# supply0.net
KiCad netlist of a schematic drawn in Altium Designer
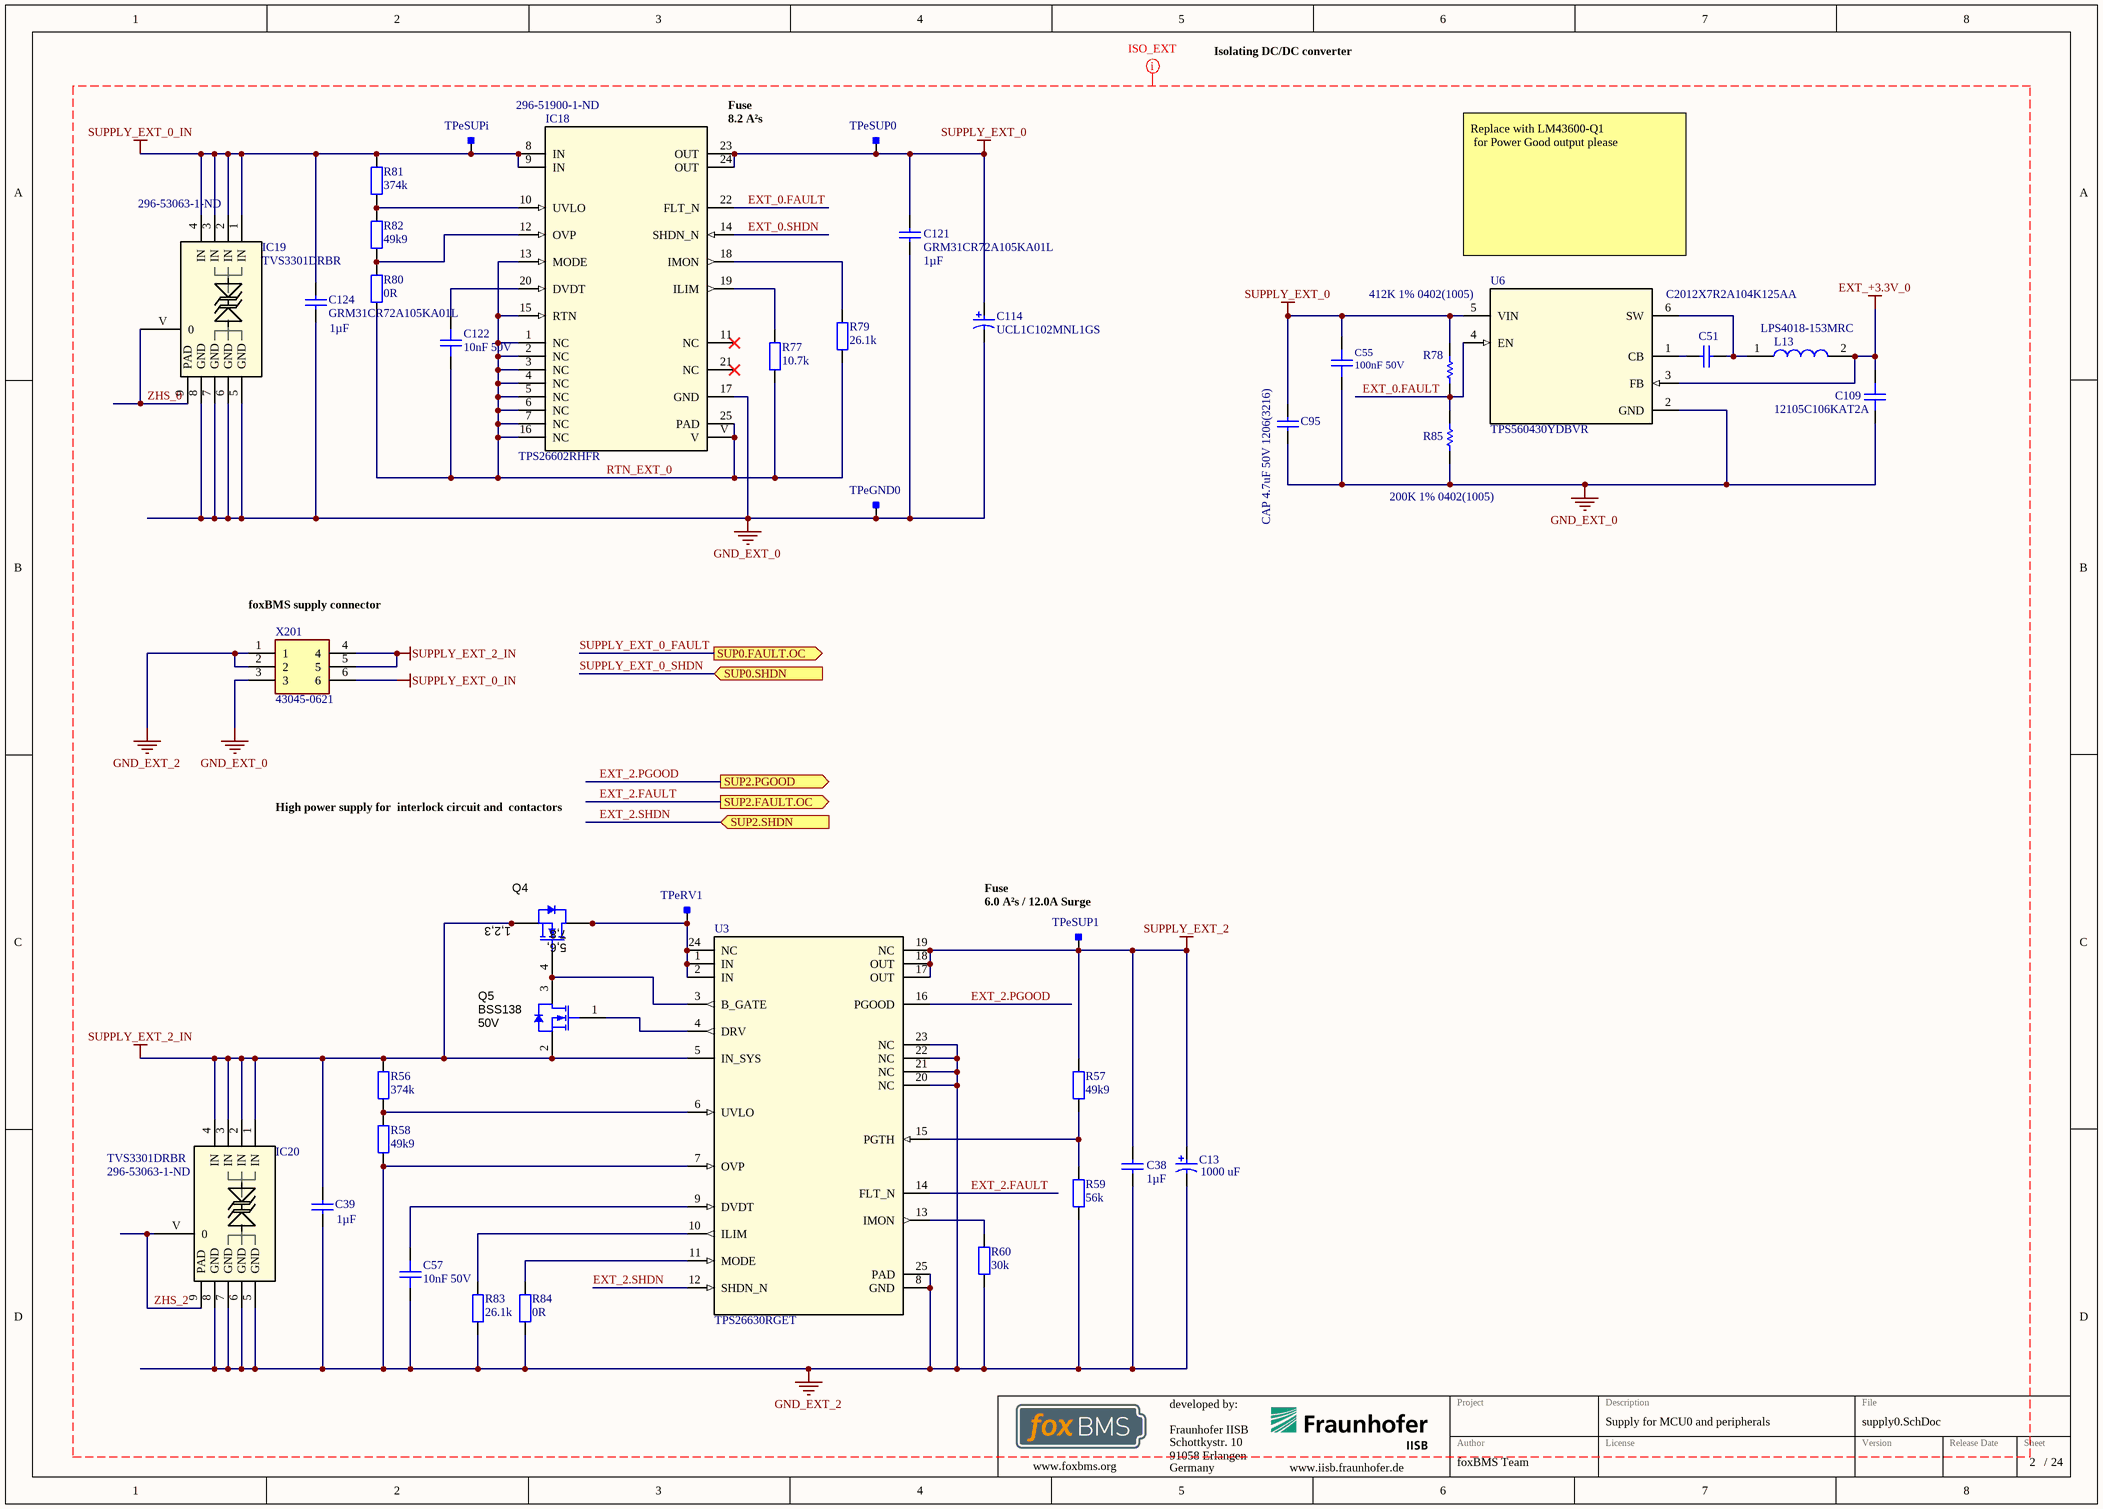
[diagram p0: supply0.SchDoc]

(export (version "E")
  (design (tool "Eeschema 10.0.6"))
  (components
    (comp (ref "C13")
      (value "UCL1C102MNL1GS")
      (footprint "NIC-UCL-10x13.5-2_V")
      (fields (field (name "MANUFACTURER") "Nichicon") (field (name "RATED CAPACITANCE") "1000 uF"))
      (libsource (lib "Altium Content Vault") (part "NIC-CAP-P-2"))
    )
    (comp (ref "C38")
      (value "GRM31CR72A105KA01L")
      (footprint "CAPC3216X180X55ML20T25")
      (description "Chip Capacitor, 1 uF, +/- 10%, 100 V, -55 to 125 degC, 1206 (3216 Metric), RoHS, Tape and Reel")
      (fields
        (field (name "TOLERANCE") "±10%")
        (field (name "MANUFACTURER") "Murata")
        (field (name "CAPACITANCE") "1µF")
      )
      (libsource (lib "master-010106") (part "CAP-NP-2"))
    )
    (comp (ref "C39")
      (value "GRM31CR72A105KA01L")
      (footprint "CAPC3216X180X55ML20T25")
      (description "Chip Capacitor, 1 uF, +/- 10%, 100 V, -55 to 125 degC, 1206 (3216 Metric), RoHS, Tape and Reel")
      (fields
        (field (name "TOLERANCE") "±10%")
        (field (name "MANUFACTURER") "Murata")
        (field (name "CAPACITANCE") "1µF")
      )
      (libsource (lib "master-010106") (part "CAP-NP-2"))
    )
    (comp (ref "C51")
      (value "C2012X7R2A104K125AA")
      (footprint "CAPC2013X145X20ML20")
      (description "Chip Capacitor, 100 nF, +/- 10%, 100 V, -55 to 1255 degC, 0805 (2012 Metric), RoHS, Tape and Reel")
      (fields (field (name "MANUFACTURER") "TDK") (field (name "TOLERANCE") "±10%"))
      (libsource (lib "Altium Content Vault") (part "CAP-NP-2"))
    )
    (comp (ref "C55")
      (value "100nF 50V")
      (footprint "0603C")
      (description "Ceramic, 100nF, ±10%, 50V, X7R, –55 to 125°C, 0603 (1608),RoHS, Automotive")
      (fields (field (name "PART NUMBER") "GCJ188R71H104KA12") (field (name "TOLERANCE") "±10%"))
      (libsource (lib "master-010106") (part "gen_C_ceramic_100n_50V_X7R_0603"))
    )
    (comp (ref "C57")
      (value "10nF 50V")
      (footprint "0402C")
      (description "Ceramic, 10nF, ±10%, 50V, X7R, –55 to 125°C, 0402 (1005),RoHS, Automotive")
      (fields (field (name "PART NUMBER") "GRT155R71H104KE01"))
      (libsource (lib "master-010106") (part "gen_C_ceramic_10n_50V_X7R_0402"))
    )
    (comp (ref "C95")
      (value "CAP 4.7uF 50V 1206(3216)")
      (footprint "CAPC1206(3216)190_N")
      (description "CAP 4.7uF 50V ±10% 1206 (3216 Metric) Thickness 1.9mm SMD")
      (fields (field (name "TOLERANCE") "Â±10%"))
      (libsource (lib "Altium Content Vault") (part "CAP"))
    )
    (comp (ref "C109")
      (value "12105C106KAT2A")
      (footprint "CAPC3225X279X50LL20T25")
      (description "Ceramic, 10uF, 50 V, -55 to 125 degC, 2-Pin SMD (1210), RoHS, Tape and Reel")
      (fields (field (name "TOLERANCE") "±10%") (field (name "MANUFACTURER") "AVX"))
      (libsource (lib "master-010106") (part "gen_C_ceramic_10u_50V_X7R_1210"))
    )
    (comp (ref "C114")
      (value "UCL1C102MNL1GS")
      (footprint "NIC-UCL-10x13.5-2_V")
      (fields (field (name "MANUFACTURER") "Nichicon"))
      (libsource (lib "Altium Content Vault") (part "NIC-CAP-P-2"))
    )
    (comp (ref "C121")
      (value "GRM31CR72A105KA01L")
      (footprint "CAPC3216X180X55ML20T25")
      (description "Chip Capacitor, 1 uF, +/- 10%, 100 V, -55 to 125 degC, 1206 (3216 Metric), RoHS, Tape and Reel")
      (fields
        (field (name "TOLERANCE") "±10%")
        (field (name "MANUFACTURER") "Murata")
        (field (name "CAPACITANCE") "1µF")
      )
      (libsource (lib "master-010106") (part "CAP-NP-2"))
    )
    (comp (ref "C122")
      (value "10nF 50V")
      (footprint "0402C")
      (description "Ceramic, 10nF, ±10%, 50V, X7R, –55 to 125°C, 0402 (1005),RoHS, Automotive")
      (fields (field (name "PART NUMBER") "GRT155R71H104KE01"))
      (libsource (lib "master-010106") (part "gen_C_ceramic_10n_50V_X7R_0402"))
    )
    (comp (ref "C124")
      (value "GRM31CR72A105KA01L")
      (footprint "CAPC3216X180X55ML20T25")
      (description "Chip Capacitor, 1 uF, +/- 10%, 100 V, -55 to 125 degC, 1206 (3216 Metric), RoHS, Tape and Reel")
      (fields
        (field (name "TOLERANCE") "±10%")
        (field (name "MANUFACTURER") "Murata")
        (field (name "CAPACITANCE") "1µF")
      )
      (libsource (lib "master-010106") (part "CAP-NP-2"))
    )
    (comp (ref "IC18")
      (value "TPS26602RHFR")
      (footprint "RHF0024A")
      (description "37V Clamped input protection")
      (fields
        (field (name "MANUFACTURER") "Texas Instruments")
        (field (name "SUPPLIER PART NUMBER 1") "296-51900-1-ND")
      )
      (libsource (lib "ti-import") (part "TPS26602RHFR"))
    )
    (comp (ref "IC19")
      (value "TVS3301DRBR")
      (footprint "DRB0008F")
      (description "TVS3301 33-V Bidirectional Flat-Clamp Surge Protection Device")
      (fields
        (field (name "MANUFACTURER") "Texas Instruments")
        (field (name "SUPPLIER PART NUMBER 1") "296-53063-1-ND")
      )
      (libsource (lib "ti-import") (part "TVS3301DRVR"))
    )
    (comp (ref "IC20")
      (value "TVS3301DRBR")
      (footprint "DRB0008F")
      (description "TVS3301 33-V Bidirectional Flat-Clamp Surge Protection Device")
      (fields
        (field (name "MANUFACTURER") "Texas Instruments")
        (field (name "SUPPLIER PART NUMBER 1") "296-53063-1-ND")
      )
      (libsource (lib "ti-import") (part "TVS3301DRVR"))
    )
    (comp (ref "L13")
      (value "LPS4018-153MRC")
      (footprint "SamacSys:LPS4018223MRC")
      (description "Inductor 15uH")
      (fields
        (field (name "MANUFACTURER_PART_NUMBER") "LPS4018-223MRC")
        (field (name "MOUSER PART NUMBER") "994-LPS4018-223MRC")
      )
      (libsource (lib "*") (part "LPS4018-223MRC"))
    )
    (comp (ref "Q4")
      (value "CSD17308Q3")
      (footprint "TRANS_NexFET_Q3")
      (description "MOSFET, N-CH, 30V, 47A, SON 3.3x3.3mm")
      (fields
        (field (name "MANUFACTURER") "Texas Instruments")
        (field (name "PUBLISHER") "Texas Instruments")
      )
      (libsource (lib "master-010106") (part "CSD17308Q3"))
    )
    (comp (ref "Q5")
      (value "BSS138")
      (footprint "SOT-23")
      (description "MOSFET, N-CH, 50V, 0.22A, SOT-23")
      (fields
        (field (name "MANUFACTURER") "Fairchild Semiconductor")
        (field (name "ALTIUM_VALUE") "50V")
        (field (name "PUBLISHER") "Texas Instruments")
      )
      (libsource (lib "master-010106") (part "BSS138"))
    )
    (comp (ref "R56")
      (value "374k")
      (footprint "0402R")
      (description "SMD Resistor 374k 0402")
      (fields (field (name "PART NUMBER") "gen_R_374k_0402"))
      (libsource (lib "master-010106") (part "gen_R_374k_0402"))
    )
    (comp (ref "R57")
      (value "49k9")
      (footprint "0402R")
      (description "SMD Resistor 49.9k 0402")
      (fields (field (name "PART NUMBER") "gen_R_49k9_0402"))
      (libsource (lib "master-010106") (part "gen_R_49k9_0402"))
    )
    (comp (ref "R58")
      (value "49k9")
      (footprint "0402R")
      (description "SMD Resistor 49.9k 0402")
      (fields (field (name "PART NUMBER") "gen_R_49k9_0402"))
      (libsource (lib "master-010106") (part "gen_R_49k9_0402"))
    )
    (comp (ref "R59")
      (value "56k")
      (footprint "0402R")
      (description "SMD Resistor 49.9k 0402")
      (fields (field (name "PART NUMBER") "gen_R_49k9_0402"))
      (libsource (lib "master-010106") (part "gen_R_49k9_0402"))
    )
    (comp (ref "R60")
      (value "30k")
      (footprint "0402R")
      (description "SMD Resistor 30k 0402")
      (fields (field (name "PART NUMBER") "gen_R_10.7k_0402"))
      (libsource (lib "master-010106") (part "gen_R_10k7_0402"))
    )
    (comp (ref "R77")
      (value "10.7k")
      (footprint "0402R")
      (description "SMD Resistor 10.7k 0402")
      (fields (field (name "PART NUMBER") "gen_R_10.7k_0402"))
      (libsource (lib "master-010106") (part "gen_R_10k7_0402"))
    )
    (comp (ref "R78")
      (value "412K 1% 0402(1005)")
      (footprint "RESC0402(1005)_L")
      (description "412K 0.063W 1% 0402 (1005 Metric)  SMD")
      (fields (field (name "TOLERANCE") "1 %") (field (name "POWER") "0.063 W"))
      (libsource (lib "Altium Content Vault") (part "RES"))
    )
    (comp (ref "R79")
      (value "26.1k")
      (footprint "0402R")
      (description "SMD Resistor 26.1k 0402")
      (fields (field (name "PART NUMBER") "gen_R_26.1k_0402"))
      (libsource (lib "master-010106") (part "gen_R_26k1_0402"))
    )
    (comp (ref "R80")
      (value "0R")
      (footprint "0402R")
      (description "SMD Resistor 0R 0402")
      (fields (field (name "PART NUMBER") "gen_R_0R_0402"))
      (libsource (lib "master-010106") (part "gen_R_0R_0402"))
    )
    (comp (ref "R81")
      (value "374k")
      (footprint "0402R")
      (description "SMD Resistor 374k 0402")
      (fields (field (name "PART NUMBER") "gen_R_374k_0402"))
      (libsource (lib "master-010106") (part "gen_R_374k_0402"))
    )
    (comp (ref "R82")
      (value "49k9")
      (footprint "0402R")
      (description "SMD Resistor 49.9k 0402")
      (fields (field (name "PART NUMBER") "gen_R_49k9_0402"))
      (libsource (lib "master-010106") (part "gen_R_49k9_0402"))
    )
    (comp (ref "R83")
      (value "26.1k")
      (footprint "0402R")
      (description "SMD Resistor 26.1k 0402")
      (fields (field (name "PART NUMBER") "gen_R_26.1k_0402"))
      (libsource (lib "master-010106") (part "gen_R_26k1_0402"))
    )
    (comp (ref "R84")
      (value "0R")
      (footprint "0402R")
      (description "SMD Resistor 0R 0402")
      (fields (field (name "PART NUMBER") "gen_R_0R_0402"))
      (libsource (lib "master-010106") (part "gen_R_0R_0402"))
    )
    (comp (ref "R85")
      (value "200K 1% 0402(1005)")
      (footprint "RESC0402(1005)_L")
      (description "200K 0.063W 1% 0402 (1005 Metric)  SMD")
      (fields (field (name "TOLERANCE") "1 %") (field (name "POWER") "0.063 W"))
      (libsource (lib "Altium Content Vault") (part "RES"))
    )
    (comp (ref "TPeGND0")
      (value "Testpoint_Square")
      (footprint "Testpoint_S1")
      (description "Testpoint, square")
      (libsource (lib "OE750") (part "Testpoint_Square"))
    )
    (comp (ref "TPeRV1")
      (value "Testpoint_Square")
      (footprint "Testpoint_S1")
      (description "Testpoint, square")
      (libsource (lib "OE750") (part "Testpoint_Square"))
    )
    (comp (ref "TPeSUP0")
      (value "Testpoint_Square")
      (footprint "Testpoint_S1")
      (description "Testpoint, square")
      (libsource (lib "OE750") (part "Testpoint_Square"))
    )
    (comp (ref "TPeSUP1")
      (value "Testpoint_Square")
      (footprint "Testpoint_S1")
      (description "Testpoint, square")
      (libsource (lib "OE750") (part "Testpoint_Square"))
    )
    (comp (ref "TPeSUPi")
      (value "Testpoint_Square")
      (footprint "Testpoint_S1")
      (description "Testpoint, square")
      (libsource (lib "OE750") (part "Testpoint_Square"))
    )
    (comp (ref "U3")
      (value "TPS26630RGET")
      (footprint "RGE0024H")
      (description "Imported")
      (fields (field (name "MANUFACTURER") "Texas Instruments") (field (name "PARTNUMBER") "TPS26630RGER"))
      (libsource (lib "ti-import") (part "TPS26630RGET"))
    )
    (comp (ref "U6")
      (value "TPS560430YDBVR")
      (footprint "DBV0006A_N")
      (description "Imported")
      (fields (field (name "MANUFACTURER") "Texas Instruments"))
      (libsource (lib "ti-import") (part "TPS560430YDBVR"))
    )
    (comp (ref "X201")
      (value "43045-0621")
      (footprint "43045-0621")
      (fields (field (name "MOUSER PART NUMBER") "538-43045-0621") (field (name "RS PART NUMBER") "6700380"))
      (libsource (lib "SamacSys") (part "43045-0621"))
    )
  )
  (nets
    (net (code "1") (name "/EXT_0.FAULT") (class "Default")
      (node (ref "IC18") (pin "22") (pinfunction "FLT_N_22") (pintype "open_collector"))
      (node (ref "R78") (pin "1") (pinfunction "1_1") (pintype "passive"))
      (node (ref "R85") (pin "2") (pinfunction "2_2") (pintype "passive"))
      (node (ref "U6") (pin "4") (pinfunction "EN_4") (pintype "input"))
    )
    (net (code "2") (name "/EXT_0.SHDN") (class "Default")
      (node (ref "IC18") (pin "14") (pinfunction "SHDN_N_14") (pintype "input"))
    )
    (net (code "3") (name "/EXT_2.FAULT") (class "Default")
      (node (ref "U3") (pin "14") (pinfunction "FLT_N_14") (pintype "open_collector"))
    )
    (net (code "4") (name "/EXT_2.PGOOD") (class "Default")
      (node (ref "U3") (pin "16") (pinfunction "PGOOD_16") (pintype "open_collector"))
    )
    (net (code "5") (name "/EXT_2.SHDN") (class "Default")
      (node (ref "U3") (pin "12") (pinfunction "SHDN_N_12") (pintype "input"))
    )
    (net (code "6") (name "/RTN_EXT_0") (class "Default")
      (node (ref "C122") (pin "2") (pinfunction "2_2") (pintype "passive"))
      (node (ref "IC18") (pin "1") (pinfunction "NC_1") (pintype "passive"))
      (node (ref "IC18") (pin "13") (pinfunction "MODE_13") (pintype "input"))
      (node (ref "IC18") (pin "15") (pinfunction "RTN_15") (pintype "input"))
      (node (ref "IC18") (pin "16") (pinfunction "NC_16") (pintype "passive"))
      (node (ref "IC18") (pin "2") (pinfunction "NC_2") (pintype "passive"))
      (node (ref "IC18") (pin "25") (pinfunction "PAD_25") (pintype "power_in"))
      (node (ref "IC18") (pin "3") (pinfunction "NC_3") (pintype "passive"))
      (node (ref "IC18") (pin "4") (pinfunction "NC_4") (pintype "passive"))
      (node (ref "IC18") (pin "5") (pinfunction "NC_5") (pintype "passive"))
      (node (ref "IC18") (pin "6") (pinfunction "NC_6") (pintype "passive"))
      (node (ref "IC18") (pin "7") (pinfunction "NC_7") (pintype "passive"))
      (node (ref "IC18") (pin "V") (pinfunction "V_V") (pintype "passive"))
      (node (ref "R77") (pin "1") (pinfunction "1_1") (pintype "passive"))
      (node (ref "R79") (pin "1") (pinfunction "1_1") (pintype "passive"))
      (node (ref "R80") (pin "1") (pinfunction "1_1") (pintype "passive"))
    )
    (net (code "9") (name "/ZHS_0") (class "Default")
      (node (ref "IC19") (pin "9") (pinfunction "PAD_9") (pintype "passive"))
      (node (ref "IC19") (pin "V") (pinfunction "0_V") (pintype "passive"))
    )
    (net (code "10") (name "/ZHS_2") (class "Default")
      (node (ref "IC20") (pin "9") (pinfunction "PAD_9") (pintype "passive"))
      (node (ref "IC20") (pin "V") (pinfunction "0_V") (pintype "passive"))
    )
    (net (code "11") (name "EXT_+3.3V_0") (class "Default")
      (node (ref "C109") (pin "2") (pinfunction "2_2") (pintype "passive"))
      (node (ref "L13") (pin "2") (pinfunction "2_2") (pintype "passive"))
      (node (ref "U6") (pin "3") (pinfunction "FB_3") (pintype "input"))
    )
    (net (code "12") (name "GND_EXT_0") (class "Default")
      (node (ref "C109") (pin "1") (pinfunction "1_1") (pintype "passive"))
      (node (ref "C114") (pin "2") (pinfunction "2_2") (pintype "passive"))
      (node (ref "C121") (pin "1") (pinfunction "1_1") (pintype "passive"))
      (node (ref "C124") (pin "1") (pinfunction "1_1") (pintype "passive"))
      (node (ref "C55") (pin "1") (pinfunction "1_1") (pintype "passive"))
      (node (ref "C95") (pin "1") (pinfunction "1_1") (pintype "passive"))
      (node (ref "IC18") (pin "17") (pinfunction "GND_17") (pintype "power_in"))
      (node (ref "IC19") (pin "5") (pinfunction "GND_5") (pintype "passive"))
      (node (ref "IC19") (pin "6") (pinfunction "GND_6") (pintype "passive"))
      (node (ref "IC19") (pin "7") (pinfunction "GND_7") (pintype "passive"))
      (node (ref "IC19") (pin "8") (pinfunction "GND_8") (pintype "passive"))
      (node (ref "R85") (pin "1") (pinfunction "1_1") (pintype "passive"))
      (node (ref "TPeGND0") (pin "1") (pinfunction "1_1") (pintype "passive"))
      (node (ref "U6") (pin "2") (pinfunction "GND_2") (pintype "power_in"))
      (node (ref "X201") (pin "3") (pinfunction "3_3") (pintype "passive"))
    )
    (net (code "13") (name "GND_EXT_2") (class "Default")
      (node (ref "C13") (pin "2") (pinfunction "2_2") (pintype "passive"))
      (node (ref "C38") (pin "1") (pinfunction "1_1") (pintype "passive"))
      (node (ref "C39") (pin "1") (pinfunction "1_1") (pintype "passive"))
      (node (ref "C57") (pin "2") (pinfunction "2_2") (pintype "passive"))
      (node (ref "IC20") (pin "5") (pinfunction "GND_5") (pintype "passive"))
      (node (ref "IC20") (pin "6") (pinfunction "GND_6") (pintype "passive"))
      (node (ref "IC20") (pin "7") (pinfunction "GND_7") (pintype "passive"))
      (node (ref "IC20") (pin "8") (pinfunction "GND_8") (pintype "passive"))
      (node (ref "R58") (pin "1") (pinfunction "1_1") (pintype "passive"))
      (node (ref "R59") (pin "1") (pinfunction "1_1") (pintype "passive"))
      (node (ref "R60") (pin "1") (pinfunction "1_1") (pintype "passive"))
      (node (ref "R83") (pin "1") (pinfunction "1_1") (pintype "passive"))
      (node (ref "R84") (pin "1") (pinfunction "1_1") (pintype "passive"))
      (node (ref "U3") (pin "20") (pinfunction "NC_20") (pintype "passive"))
      (node (ref "U3") (pin "21") (pinfunction "NC_21") (pintype "passive"))
      (node (ref "U3") (pin "22") (pinfunction "NC_22") (pintype "passive"))
      (node (ref "U3") (pin "23") (pinfunction "NC_23") (pintype "passive"))
      (node (ref "U3") (pin "25") (pinfunction "PAD_25") (pintype "power_in"))
      (node (ref "U3") (pin "7") (pinfunction "OVP_7") (pintype "input"))
      (node (ref "U3") (pin "8") (pinfunction "GND_8") (pintype "power_in"))
      (node (ref "X201") (pin "1") (pinfunction "1_1") (pintype "passive"))
      (node (ref "X201") (pin "2") (pinfunction "2_2") (pintype "passive"))
    )
    (net (code "14") (name "Net-(IC18-DVDT)") (class "Default")
      (node (ref "C122") (pin "1") (pinfunction "1_1") (pintype "passive"))
      (node (ref "IC18") (pin "20") (pinfunction "DVDT_20") (pintype "input"))
    )
    (net (code "15") (name "Net-(IC18-ILIM)") (class "Default")
      (node (ref "IC18") (pin "19") (pinfunction "ILIM_19") (pintype "output"))
      (node (ref "R77") (pin "2") (pinfunction "2_2") (pintype "passive"))
    )
    (net (code "16") (name "Net-(IC18-IMON)") (class "Default")
      (node (ref "IC18") (pin "18") (pinfunction "IMON_18") (pintype "output"))
      (node (ref "R79") (pin "2") (pinfunction "2_2") (pintype "passive"))
    )
    (net (code "17") (name "Net-(IC18-OVP)") (class "Default")
      (node (ref "IC18") (pin "12") (pinfunction "OVP_12") (pintype "input"))
      (node (ref "R80") (pin "2") (pinfunction "2_2") (pintype "passive"))
      (node (ref "R82") (pin "1") (pinfunction "1_1") (pintype "passive"))
    )
    (net (code "18") (name "Net-(IC18-UVLO)") (class "Default")
      (node (ref "IC18") (pin "10") (pinfunction "UVLO_10") (pintype "input"))
      (node (ref "R81") (pin "1") (pinfunction "1_1") (pintype "passive"))
      (node (ref "R82") (pin "2") (pinfunction "2_2") (pintype "passive"))
    )
    (net (code "19") (name "Net-(Q4-D-Pad5)") (class "Default")
      (node (ref "Q4") (pin "5") (pinfunction "D_5") (pintype "passive"))
      (node (ref "Q4") (pin "6") (pinfunction "D_6") (pintype "passive"))
      (node (ref "Q4") (pin "7") (pinfunction "D_7") (pintype "passive"))
      (node (ref "Q4") (pin "8") (pinfunction "D_8") (pintype "passive"))
      (node (ref "TPeRV1") (pin "1") (pinfunction "1_1") (pintype "passive"))
      (node (ref "U3") (pin "1") (pinfunction "IN_1") (pintype "power_in"))
      (node (ref "U3") (pin "2") (pinfunction "IN_2") (pintype "power_in"))
      (node (ref "U3") (pin "24") (pinfunction "NC_24") (pintype "passive"))
    )
    (net (code "20") (name "Net-(Q4-G)") (class "Default")
      (node (ref "Q4") (pin "4") (pinfunction "G_4") (pintype "passive"))
      (node (ref "Q5") (pin "3") (pinfunction "D_3") (pintype "passive"))
      (node (ref "U3") (pin "3") (pinfunction "B_GATE_3") (pintype "output"))
    )
    (net (code "21") (name "Net-(Q5-G)") (class "Default")
      (node (ref "Q5") (pin "1") (pinfunction "G_1") (pintype "passive"))
      (node (ref "U3") (pin "4") (pinfunction "DRV_4") (pintype "output"))
    )
    (net (code "22") (name "Net-(U3-DVDT)") (class "Default")
      (node (ref "C57") (pin "1") (pinfunction "1_1") (pintype "passive"))
      (node (ref "U3") (pin "9") (pinfunction "DVDT_9") (pintype "input"))
    )
    (net (code "23") (name "Net-(U3-ILIM)") (class "Default")
      (node (ref "R83") (pin "2") (pinfunction "2_2") (pintype "passive"))
      (node (ref "U3") (pin "10") (pinfunction "ILIM_10") (pintype "output"))
    )
    (net (code "24") (name "Net-(U3-IMON)") (class "Default")
      (node (ref "R60") (pin "2") (pinfunction "2_2") (pintype "passive"))
      (node (ref "U3") (pin "13") (pinfunction "IMON_13") (pintype "output"))
    )
    (net (code "25") (name "Net-(U3-MODE)") (class "Default")
      (node (ref "R84") (pin "2") (pinfunction "2_2") (pintype "passive"))
      (node (ref "U3") (pin "11") (pinfunction "MODE_11") (pintype "input"))
    )
    (net (code "26") (name "Net-(U3-PGTH)") (class "Default")
      (node (ref "R57") (pin "1") (pinfunction "1_1") (pintype "passive"))
      (node (ref "R59") (pin "2") (pinfunction "2_2") (pintype "passive"))
      (node (ref "U3") (pin "15") (pinfunction "PGTH_15") (pintype "input"))
    )
    (net (code "27") (name "Net-(U3-UVLO)") (class "Default")
      (node (ref "R56") (pin "1") (pinfunction "1_1") (pintype "passive"))
      (node (ref "R58") (pin "2") (pinfunction "2_2") (pintype "passive"))
      (node (ref "U3") (pin "6") (pinfunction "UVLO_6") (pintype "input"))
    )
    (net (code "28") (name "Net-(U6-CB)") (class "Default")
      (node (ref "C51") (pin "1") (pinfunction "1_1") (pintype "passive"))
      (node (ref "U6") (pin "1") (pinfunction "CB_1") (pintype "power_in"))
    )
    (net (code "29") (name "Net-(U6-SW)") (class "Default")
      (node (ref "C51") (pin "2") (pinfunction "2_2") (pintype "passive"))
      (node (ref "L13") (pin "1") (pinfunction "1_1") (pintype "passive"))
      (node (ref "U6") (pin "6") (pinfunction "SW_6") (pintype "power_in"))
    )
    (net (code "30") (name "SUPPLY_EXT_0") (class "Default")
      (node (ref "C114") (pin "1") (pinfunction "1_1") (pintype "passive"))
      (node (ref "C121") (pin "2") (pinfunction "2_2") (pintype "passive"))
      (node (ref "C55") (pin "2") (pinfunction "2_2") (pintype "passive"))
      (node (ref "C95") (pin "2") (pinfunction "2_2") (pintype "passive"))
      (node (ref "IC18") (pin "23") (pinfunction "OUT_23") (pintype "power_in"))
      (node (ref "IC18") (pin "24") (pinfunction "OUT_24") (pintype "power_in"))
      (node (ref "R78") (pin "2") (pinfunction "2_2") (pintype "passive"))
      (node (ref "TPeSUP0") (pin "1") (pinfunction "1_1") (pintype "passive"))
      (node (ref "U6") (pin "5") (pinfunction "VIN_5") (pintype "power_in"))
    )
    (net (code "31") (name "SUPPLY_EXT_0_IN") (class "Default")
      (node (ref "C124") (pin "2") (pinfunction "2_2") (pintype "passive"))
      (node (ref "IC18") (pin "8") (pinfunction "IN_8") (pintype "power_in"))
      (node (ref "IC18") (pin "9") (pinfunction "IN_9") (pintype "power_in"))
      (node (ref "IC19") (pin "1") (pinfunction "IN_1") (pintype "passive"))
      (node (ref "IC19") (pin "2") (pinfunction "IN_2") (pintype "passive"))
      (node (ref "IC19") (pin "3") (pinfunction "IN_3") (pintype "passive"))
      (node (ref "IC19") (pin "4") (pinfunction "IN_4") (pintype "passive"))
      (node (ref "R81") (pin "2") (pinfunction "2_2") (pintype "passive"))
      (node (ref "TPeSUPi") (pin "1") (pinfunction "1_1") (pintype "passive"))
      (node (ref "X201") (pin "6") (pinfunction "6_6") (pintype "passive"))
    )
    (net (code "32") (name "SUPPLY_EXT_2") (class "Default")
      (node (ref "C13") (pin "1") (pinfunction "1_1") (pintype "passive"))
      (node (ref "C38") (pin "2") (pinfunction "2_2") (pintype "passive"))
      (node (ref "R57") (pin "2") (pinfunction "2_2") (pintype "passive"))
      (node (ref "TPeSUP1") (pin "1") (pinfunction "1_1") (pintype "passive"))
      (node (ref "U3") (pin "17") (pinfunction "OUT_17") (pintype "power_in"))
      (node (ref "U3") (pin "18") (pinfunction "OUT_18") (pintype "power_in"))
      (node (ref "U3") (pin "19") (pinfunction "NC_19") (pintype "passive"))
    )
    (net (code "33") (name "SUPPLY_EXT_2_IN") (class "Default")
      (node (ref "C39") (pin "2") (pinfunction "2_2") (pintype "passive"))
      (node (ref "IC20") (pin "1") (pinfunction "IN_1") (pintype "passive"))
      (node (ref "IC20") (pin "2") (pinfunction "IN_2") (pintype "passive"))
      (node (ref "IC20") (pin "3") (pinfunction "IN_3") (pintype "passive"))
      (node (ref "IC20") (pin "4") (pinfunction "IN_4") (pintype "passive"))
      (node (ref "Q4") (pin "1") (pinfunction "S_1") (pintype "passive"))
      (node (ref "Q4") (pin "2") (pinfunction "S_2") (pintype "passive"))
      (node (ref "Q4") (pin "3") (pinfunction "S_3") (pintype "passive"))
      (node (ref "Q5") (pin "2") (pinfunction "S_2") (pintype "passive"))
      (node (ref "R56") (pin "2") (pinfunction "2_2") (pintype "passive"))
      (node (ref "U3") (pin "5") (pinfunction "IN_SYS_5") (pintype "power_in"))
      (node (ref "X201") (pin "4") (pinfunction "4_4") (pintype "passive"))
      (node (ref "X201") (pin "5") (pinfunction "5_5") (pintype "passive"))
    )
    (net (code "34") (name "unconnected-(IC18-NC-Pad11)") (class "Default")
      (node (ref "IC18") (pin "11") (pinfunction "NC_11") (pintype "passive+no_connect"))
    )
    (net (code "35") (name "unconnected-(IC18-NC-Pad21)") (class "Default")
      (node (ref "IC18") (pin "21") (pinfunction "NC_21") (pintype "passive+no_connect"))
    )
  )
)
